# DM1092_IMU.net
KiCad netlist of a schematic drawn in Altium Designer
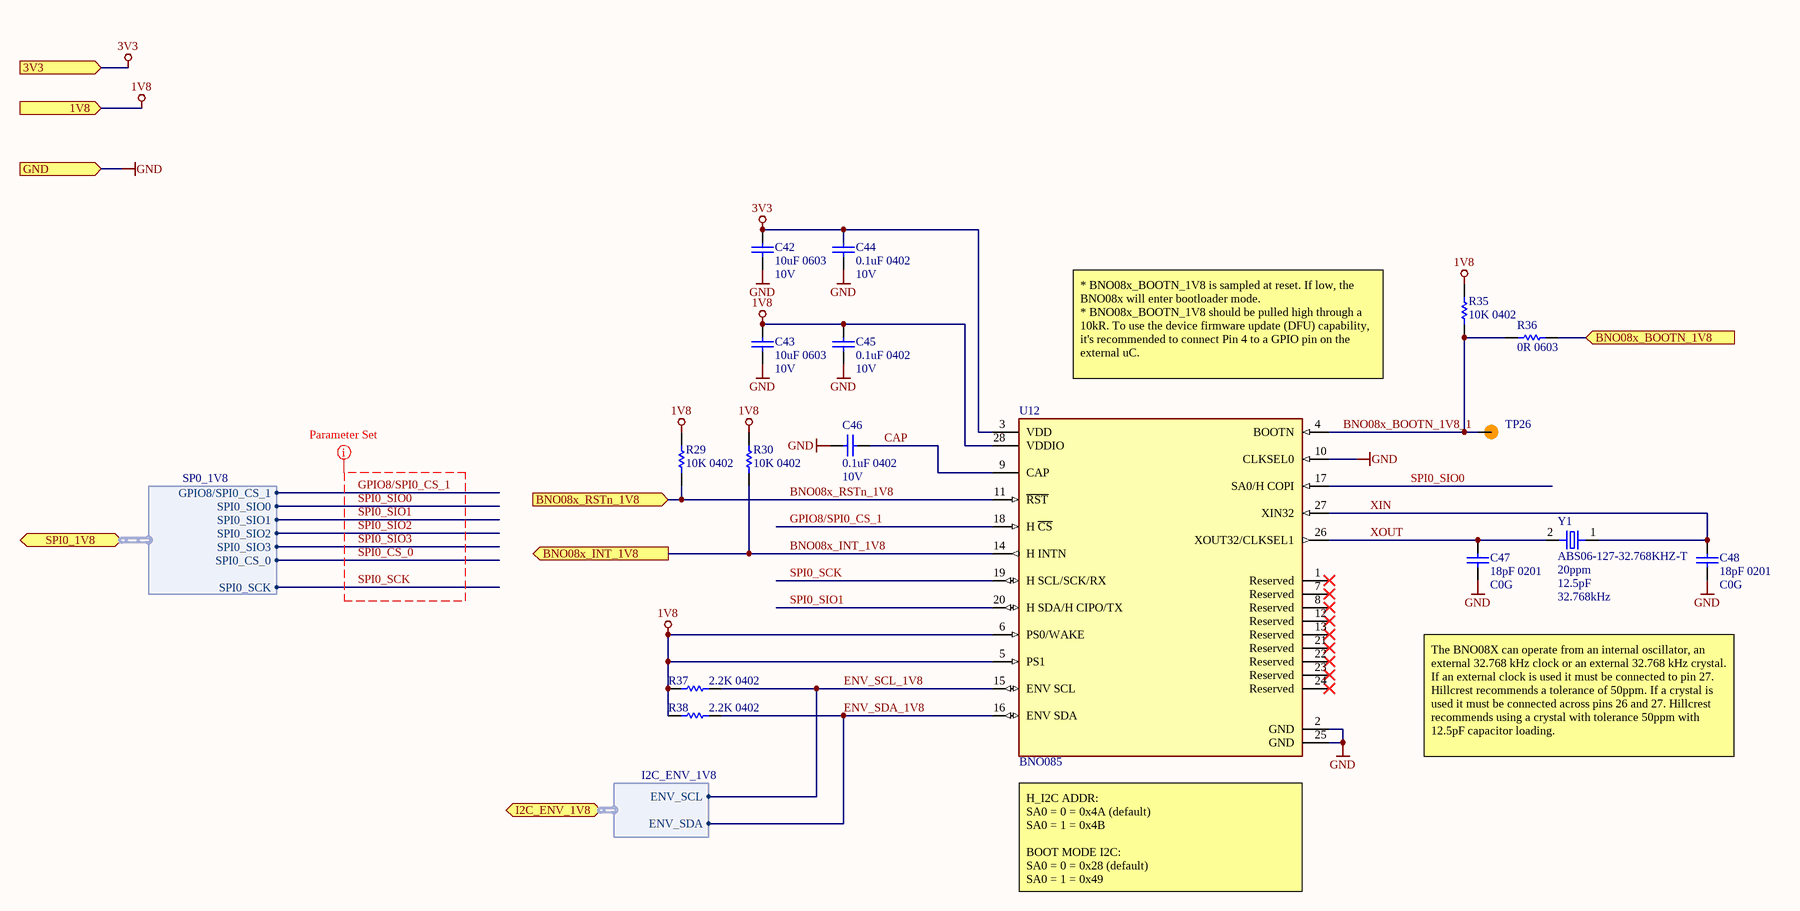
[diagram p0: DM1092_IMU.SchDoc]

(export (version "E")
  (design (tool "Eeschema 10.0.6"))
  (components
    (comp (ref "C42")
      (value "10uF 0603")
      (footprint "CAP_Altium_Vault_Generic:CAPC0603(1608)100_N")
      (description "CAP CER 10UF 10V X5R 0603 20%")
      (fields (field (name "TOLERANCE") "20%") (field (name "VOLTAGE RATING") "10V"))
      (libsource (lib "LuxonisMaster") (part "GRM188R61A106ME69D"))
    )
    (comp (ref "C43")
      (value "10uF 0603")
      (footprint "CAP_Altium_Vault_Generic:CAPC0603(1608)100_L")
      (description "CAP CER 10UF 10V X5R 0603 20%")
      (fields (field (name "TOLERANCE") "20%") (field (name "VOLTAGE RATING") "10V"))
      (libsource (lib "LuxonisMaster") (part "GRM188R61A106ME69D"))
    )
    (comp (ref "C44")
      (value "0.1uF 0402")
      (footprint "CAP_Altium_Vault_Generic:CAPC0402(1005)70_N")
      (description "CAP CER 0.1UF 10V X7R 0402 5%")
      (fields (field (name "TOLERANCE") "5%") (field (name "VOLTAGE RATING") "10V"))
      (libsource (lib "LuxonisMaster") (part "GRM155R71A104JA01D"))
    )
    (comp (ref "C45")
      (value "0.1uF 0402")
      (footprint "CAP_Altium_Vault_Generic:CAPC0402(1005)70_L")
      (description "CAP CER 0.1UF 10V X7R 0402 5%")
      (fields (field (name "TOLERANCE") "5%") (field (name "VOLTAGE RATING") "10V"))
      (libsource (lib "LuxonisMaster") (part "GRM155R71A104JA01D"))
    )
    (comp (ref "C46")
      (value "0.1uF 0402")
      (footprint "CAP_Altium_Vault_Generic:CAPC0402(1005)70_N")
      (description "CAP CER 0.1UF 10V X7R 0402 5%")
      (fields (field (name "TOLERANCE") "5%") (field (name "VOLTAGE RATING") "10V"))
      (libsource (lib "LuxonisMaster") (part "GRM155R71A104JA01D"))
    )
    (comp (ref "C47")
      (value "18pF 0201")
      (footprint "CAPC0201(0603)33_N")
      (description "Cap Ceramic 18pF 25V C0G 1% Pad SMD 0201 125C T/R")
      (fields (field (name "TOLERANCE") "1%") (field (name "DIELECTRIC") "C0G"))
      (libsource (lib "DM1092_R0M0E0") (part "GRM0335C1E180FA01D"))
    )
    (comp (ref "C48")
      (value "18pF 0201")
      (footprint "CAPC0201(0603)33_N")
      (description "Cap Ceramic 18pF 25V C0G 1% Pad SMD 0201 125C T/R")
      (fields (field (name "TOLERANCE") "1%") (field (name "DIELECTRIC") "C0G"))
      (libsource (lib "DM1092_R0M0E0") (part "GRM0335C1E180FA01D"))
    )
    (comp (ref "R29")
      (value "10K 0402")
      (footprint "RES_Altium_Vault_Generic:RESC0402(1005)_N")
      (fields (field (name "TOLERANCE") "1%"))
      (libsource (lib "LuxonisMaster") (part "RC0402FR-1310KL"))
    )
    (comp (ref "R30")
      (value "10K 0402")
      (footprint "RES_Altium_Vault_Generic:RESC0402(1005)_N")
      (fields (field (name "TOLERANCE") "1%"))
      (libsource (lib "LuxonisMaster") (part "RC0402FR-1310KL"))
    )
    (comp (ref "R35")
      (value "10K 0402")
      (footprint "RES_Altium_Vault_Generic:RESC0402(1005)_N")
      (fields (field (name "TOLERANCE") "1%"))
      (libsource (lib "LuxonisMaster") (part "RC0402FR-1310KL"))
    )
    (comp (ref "R36")
      (value "0R 0603")
      (footprint "RES_Altium_Vault_Generic:RESC0603(1608)_N")
      (fields (field (name "TOLERANCE") "5%"))
      (libsource (lib "LuxonisMaster") (part "CRCW06030000Z0EA"))
    )
    (comp (ref "R37")
      (value "2.2K 0402")
      (footprint "RES_Altium_Vault_Generic:RESC0402(1005)_N")
      (description "RES SMD 2.2K OHM 1% 1/16W 0402")
      (fields (field (name "TOLERANCE") "1%"))
      (libsource (lib "LuxonisMaster") (part "RC0402FR-072K2L"))
    )
    (comp (ref "R38")
      (value "2.2K 0402")
      (footprint "RES_Altium_Vault_Generic:RESC0402(1005)_N")
      (description "RES SMD 2.2K OHM 1% 1/16W 0402")
      (fields (field (name "TOLERANCE") "1%"))
      (libsource (lib "LuxonisMaster") (part "RC0402FR-072K2L"))
    )
    (comp (ref "TP26")
      (value "TP100_200_NS")
      (footprint "LuxonisMaster:TP100_200_NS")
      (libsource (lib "LuxonisMaster") (part "TEST_POINT"))
    )
    (comp (ref "U12")
      (value "BNO085")
      (footprint "BNO085")
      (description "IMU ACCEL/GYRO/MAG I2C 32BIT")
      (libsource (lib "DM1092_R0M0E0") (part "BNO085"))
    )
    (comp (ref "Y1")
      (value "ABS06-127-32.768KHZ-T")
      (footprint "ABS06-127-32.768KHZ-T")
      (description "CRYSTAL 32.768kHz ±20ppm Crystal 12.5pF 90 kOhms 2-SMD, No Lead")
      (fields
        (field (name "FREQUENCY TOLERANCE") "20ppm")
        (field (name "LOAD CAPACITANCE") "12.5pF")
        (field (name "FREQUENCY") "32.768kHz")
      )
      (libsource (lib "DM1092_R0M0E0") (part "ABS06-127-32.768KHZ-T"))
    )
  )
  (nets
    (net (code "3") (name "/BNO08x_BOOTN_1V8") (class "Default")
      (node (ref "R36") (pin "2") (pinfunction "2_2") (pintype "passive"))
    )
    (net (code "4") (name "/BNO08x_BOOTN_1V8_1") (class "Default")
      (node (ref "R35") (pin "1") (pinfunction "1_1") (pintype "passive"))
      (node (ref "R36") (pin "1") (pinfunction "1_1") (pintype "passive"))
      (node (ref "TP26") (pin "1") (pintype "passive"))
      (node (ref "U12") (pin "4") (pinfunction "BOOTN_4") (pintype "input"))
    )
    (net (code "5") (name "/BNO08x_INT_1V8") (class "Default")
      (node (ref "R30") (pin "1") (pinfunction "1_1") (pintype "passive"))
      (node (ref "U12") (pin "14") (pinfunction "H_INTN_14") (pintype "output"))
    )
    (net (code "6") (name "/BNO08x_RSTn_1V8") (class "Default")
      (node (ref "R29") (pin "1") (pinfunction "1_1") (pintype "passive"))
      (node (ref "U12") (pin "11") (pinfunction "~{RST}_11") (pintype "input"))
    )
    (net (code "7") (name "/CAP") (class "Default")
      (node (ref "C46") (pin "1") (pinfunction "1_1") (pintype "passive"))
      (node (ref "U12") (pin "9") (pinfunction "CAP_9") (pintype "passive"))
    )
    (net (code "8") (name "/ENV_SCL_1V8") (class "Default")
      (node (ref "R37") (pin "2") (pinfunction "2_2") (pintype "passive"))
      (node (ref "U12") (pin "15") (pinfunction "ENV_SCL_15") (pintype "bidirectional"))
    )
    (net (code "9") (name "/ENV_SDA_1V8") (class "Default")
      (node (ref "R38") (pin "2") (pinfunction "2_2") (pintype "passive"))
      (node (ref "U12") (pin "16") (pinfunction "ENV_SDA_16") (pintype "bidirectional"))
    )
    (net (code "10") (name "/GPIO8{slash}SPI0_CS_1") (class "Default")
      (node (ref "U12") (pin "18") (pinfunction "H_~{CS}_18") (pintype "input"))
    )
    (net (code "12") (name "/SPI0_SCK") (class "Default")
      (node (ref "U12") (pin "19") (pinfunction "H_SCL/SCK/RX_19") (pintype "bidirectional"))
    )
    (net (code "13") (name "/SPI0_SIO0") (class "Default")
      (node (ref "U12") (pin "17") (pinfunction "SA0/H_COPI_17") (pintype "input"))
    )
    (net (code "14") (name "/SPI0_SIO1") (class "Default")
      (node (ref "U12") (pin "20") (pinfunction "H_SDA/H_CIPO/TX_20") (pintype "bidirectional"))
    )
    (net (code "17") (name "/XIN") (class "Default")
      (node (ref "C48") (pin "2") (pinfunction "2_2") (pintype "passive"))
      (node (ref "U12") (pin "27") (pinfunction "XIN32_27") (pintype "input"))
      (node (ref "Y1") (pin "1") (pinfunction "1_1") (pintype "passive"))
    )
    (net (code "18") (name "/XOUT") (class "Default")
      (node (ref "C47") (pin "2") (pinfunction "2_2") (pintype "passive"))
      (node (ref "U12") (pin "26") (pinfunction "XOUT32/CLKSEL1_26") (pintype "output"))
      (node (ref "Y1") (pin "2") (pinfunction "2_2") (pintype "passive"))
    )
    (net (code "21") (name "1V8") (class "Default")
      (node (ref "C43") (pin "2") (pinfunction "2_2") (pintype "passive"))
      (node (ref "C45") (pin "2") (pinfunction "2_2") (pintype "passive"))
      (node (ref "R29") (pin "2") (pinfunction "2_2") (pintype "passive"))
      (node (ref "R30") (pin "2") (pinfunction "2_2") (pintype "passive"))
      (node (ref "R35") (pin "2") (pinfunction "2_2") (pintype "passive"))
      (node (ref "R37") (pin "1") (pinfunction "1_1") (pintype "passive"))
      (node (ref "R38") (pin "1") (pinfunction "1_1") (pintype "passive"))
      (node (ref "U12") (pin "28") (pinfunction "VDDIO_28") (pintype "power_in"))
      (node (ref "U12") (pin "5") (pinfunction "PS1_5") (pintype "input"))
      (node (ref "U12") (pin "6") (pinfunction "PS0/WAKE_6") (pintype "input"))
    )
    (net (code "22") (name "3V3") (class "Default")
      (node (ref "C42") (pin "2") (pinfunction "2_2") (pintype "passive"))
      (node (ref "C44") (pin "2") (pinfunction "2_2") (pintype "passive"))
      (node (ref "U12") (pin "3") (pinfunction "VDD_3") (pintype "power_in"))
    )
    (net (code "23") (name "GND") (class "Default")
      (node (ref "C42") (pin "1") (pinfunction "1_1") (pintype "passive"))
      (node (ref "C43") (pin "1") (pinfunction "1_1") (pintype "passive"))
      (node (ref "C44") (pin "1") (pinfunction "1_1") (pintype "passive"))
      (node (ref "C45") (pin "1") (pinfunction "1_1") (pintype "passive"))
      (node (ref "C46") (pin "2") (pinfunction "2_2") (pintype "passive"))
      (node (ref "C47") (pin "1") (pinfunction "1_1") (pintype "passive"))
      (node (ref "C48") (pin "1") (pinfunction "1_1") (pintype "passive"))
      (node (ref "U12") (pin "10") (pinfunction "CLKSEL0_10") (pintype "input"))
      (node (ref "U12") (pin "2") (pinfunction "GND_2") (pintype "power_in"))
      (node (ref "U12") (pin "25") (pinfunction "GND_25") (pintype "power_in"))
    )
    (net (code "24") (name "unconnected-(U12-Reserved-Pad1)") (class "Default")
      (node (ref "U12") (pin "1") (pinfunction "Reserved_1") (pintype "passive+no_connect"))
    )
    (net (code "25") (name "unconnected-(U12-Reserved-Pad7)") (class "Default")
      (node (ref "U12") (pin "7") (pinfunction "Reserved_7") (pintype "passive+no_connect"))
    )
    (net (code "26") (name "unconnected-(U12-Reserved-Pad8)") (class "Default")
      (node (ref "U12") (pin "8") (pinfunction "Reserved_8") (pintype "passive+no_connect"))
    )
    (net (code "27") (name "unconnected-(U12-Reserved-Pad12)") (class "Default")
      (node (ref "U12") (pin "12") (pinfunction "Reserved_12") (pintype "passive+no_connect"))
    )
    (net (code "28") (name "unconnected-(U12-Reserved-Pad13)") (class "Default")
      (node (ref "U12") (pin "13") (pinfunction "Reserved_13") (pintype "passive+no_connect"))
    )
    (net (code "29") (name "unconnected-(U12-Reserved-Pad21)") (class "Default")
      (node (ref "U12") (pin "21") (pinfunction "Reserved_21") (pintype "passive+no_connect"))
    )
    (net (code "30") (name "unconnected-(U12-Reserved-Pad22)") (class "Default")
      (node (ref "U12") (pin "22") (pinfunction "Reserved_22") (pintype "passive+no_connect"))
    )
    (net (code "31") (name "unconnected-(U12-Reserved-Pad23)") (class "Default")
      (node (ref "U12") (pin "23") (pinfunction "Reserved_23") (pintype "passive+no_connect"))
    )
    (net (code "32") (name "unconnected-(U12-Reserved-Pad24)") (class "Default")
      (node (ref "U12") (pin "24") (pinfunction "Reserved_24") (pintype "passive+no_connect"))
    )
  )
)
